# tinybord.net
KiCad netlist of a schematic drawn in Altium Designer
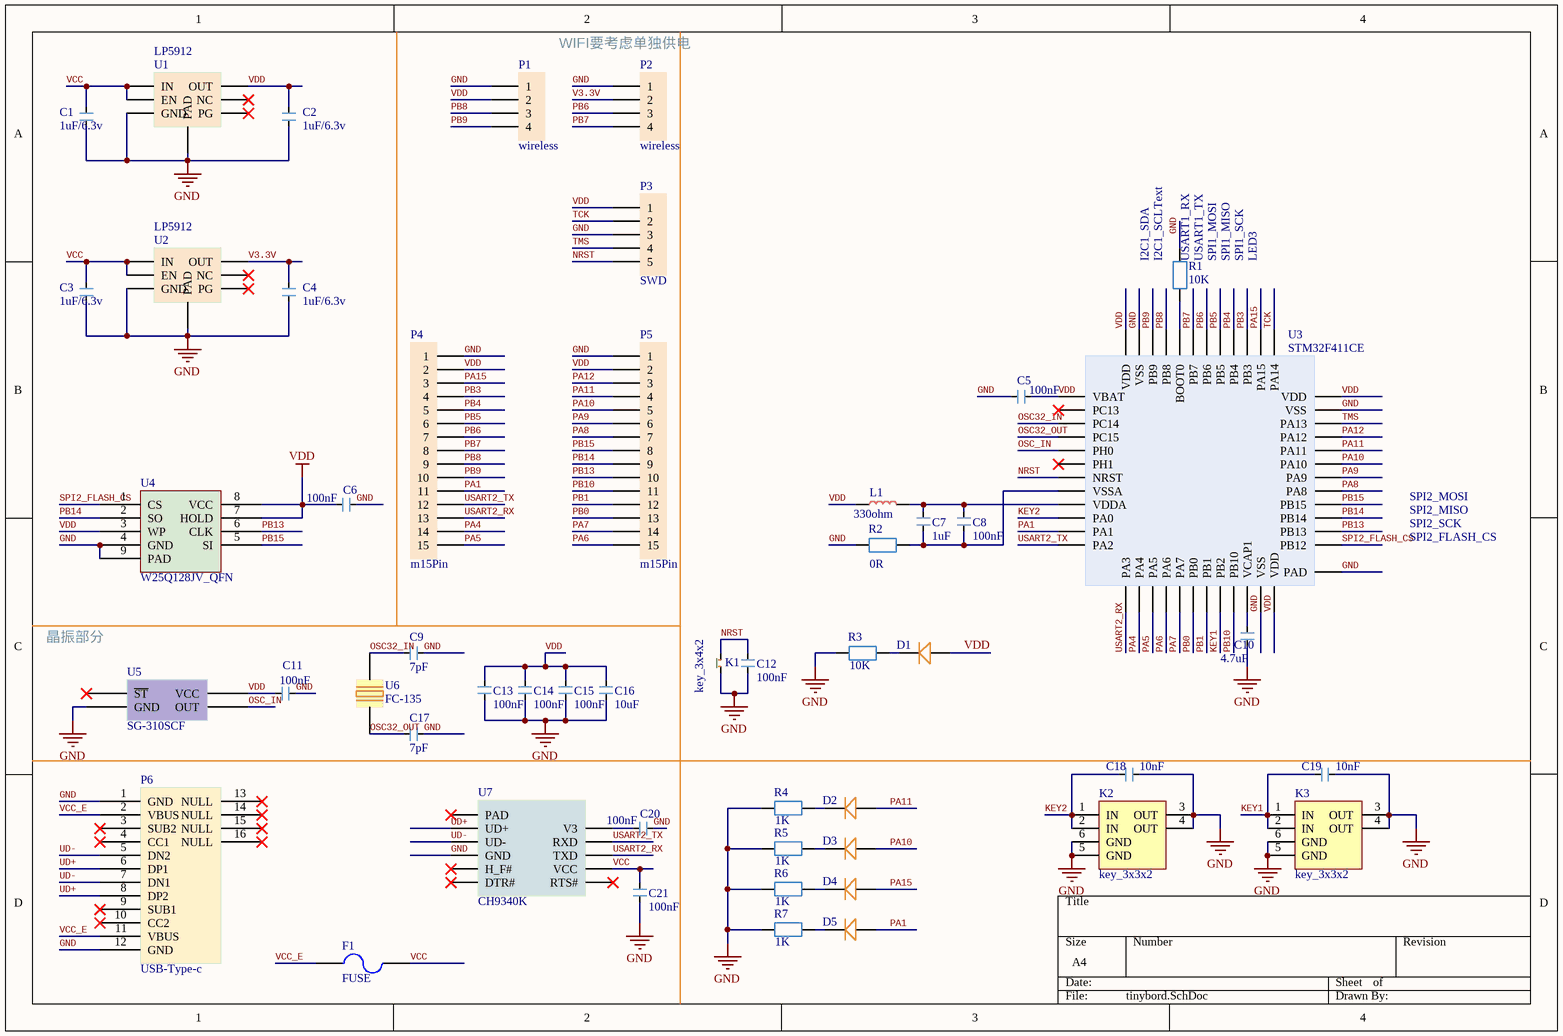
[diagram p0: tinybord.SchDoc]

(export (version "E")
  (design (tool "Eeschema 10.0.6"))
  (components
    (comp (ref "C1")
      (value "1uF/6.3v")
      (footprint "C0603")
      (description "陶瓷电容")
      (fields (field (name "Comment") "C0603"))
      (libsource (lib "DemoSchlib") (part "C0603"))
    )
    (comp (ref "C2")
      (value "1uF/6.3v")
      (footprint "C0603")
      (description "陶瓷电容")
      (fields (field (name "Comment") "C0603"))
      (libsource (lib "DemoSchlib") (part "C0603"))
    )
    (comp (ref "C3")
      (value "1uF/6.3v")
      (footprint "C0603")
      (description "陶瓷电容")
      (fields (field (name "Comment") "C0603"))
      (libsource (lib "DemoSchlib") (part "C0603"))
    )
    (comp (ref "C4")
      (value "1uF/6.3v")
      (footprint "C0603")
      (description "陶瓷电容")
      (fields (field (name "Comment") "C0603"))
      (libsource (lib "DemoSchlib") (part "C0603"))
    )
    (comp (ref "C5")
      (value "100nF")
      (footprint "C0603")
      (description "陶瓷电容")
      (fields (field (name "Comment") "C0603"))
      (libsource (lib "DemoSchlib") (part "C0603"))
    )
    (comp (ref "C6")
      (value "100nF")
      (footprint "C0603")
      (description "陶瓷电容")
      (fields (field (name "Comment") "C0603"))
      (libsource (lib "DemoSchlib") (part "C0603"))
    )
    (comp (ref "C7")
      (value "1uF")
      (footprint "C0603")
      (description "陶瓷电容")
      (fields (field (name "Comment") "C0603"))
      (libsource (lib "DemoSchlib") (part "C0603"))
    )
    (comp (ref "C8")
      (value "100nF")
      (footprint "C0603")
      (description "陶瓷电容")
      (fields (field (name "Comment") "C0603"))
      (libsource (lib "DemoSchlib") (part "C0603"))
    )
    (comp (ref "C9")
      (value "7pF")
      (footprint "C0603")
      (description "陶瓷电容")
      (fields (field (name "Comment") "C0603"))
      (libsource (lib "DemoSchlib") (part "C0603"))
    )
    (comp (ref "C10")
      (value "4.7uF")
      (footprint "C0603")
      (description "陶瓷电容")
      (fields (field (name "Comment") "C0603"))
      (libsource (lib "DemoSchlib") (part "C0603"))
    )
    (comp (ref "C11")
      (value "100nF")
      (footprint "C0603")
      (description "陶瓷电容")
      (fields (field (name "Comment") "C0603"))
      (libsource (lib "DemoSchlib") (part "C0603"))
    )
    (comp (ref "C12")
      (value "100nF")
      (footprint "C0603")
      (description "陶瓷电容")
      (fields (field (name "Comment") "C0603"))
      (libsource (lib "DemoSchlib") (part "C0603"))
    )
    (comp (ref "C13")
      (value "100nF")
      (footprint "C0603")
      (description "陶瓷电容")
      (fields (field (name "Comment") "C0603"))
      (libsource (lib "DemoSchlib") (part "C0603"))
    )
    (comp (ref "C14")
      (value "100nF")
      (footprint "C0603")
      (description "陶瓷电容")
      (fields (field (name "Comment") "C0603"))
      (libsource (lib "DemoSchlib") (part "C0603"))
    )
    (comp (ref "C15")
      (value "100nF")
      (footprint "C0603")
      (description "陶瓷电容")
      (fields (field (name "Comment") "C0603"))
      (libsource (lib "DemoSchlib") (part "C0603"))
    )
    (comp (ref "C16")
      (value "10uF")
      (footprint "C0603")
      (description "陶瓷电容")
      (fields (field (name "Comment") "C0603"))
      (libsource (lib "DemoSchlib") (part "C0603"))
    )
    (comp (ref "C17")
      (value "7pF")
      (footprint "C0603")
      (description "陶瓷电容")
      (fields (field (name "Comment") "C0603"))
      (libsource (lib "DemoSchlib") (part "C0603"))
    )
    (comp (ref "C18")
      (value "10nF")
      (footprint "C0603")
      (description "陶瓷电容")
      (fields (field (name "Comment") "C0603"))
      (libsource (lib "DemoSchlib") (part "C0603"))
    )
    (comp (ref "C19")
      (value "10nF")
      (footprint "C0603")
      (description "陶瓷电容")
      (fields (field (name "Comment") "C0603"))
      (libsource (lib "DemoSchlib") (part "C0603"))
    )
    (comp (ref "C20")
      (value "100nF")
      (footprint "C0603")
      (description "陶瓷电容")
      (fields (field (name "Comment") "C0603"))
      (libsource (lib "DemoSchlib") (part "C0603"))
    )
    (comp (ref "C21")
      (value "100nF")
      (footprint "C0603")
      (description "陶瓷电容")
      (fields (field (name "Comment") "C0603"))
      (libsource (lib "DemoSchlib") (part "C0603"))
    )
    (comp (ref "D1")
      (value "L0603")
      (footprint "led0603")
      (description "LED")
      (libsource (lib "DemoSchlib") (part "L0603"))
    )
    (comp (ref "D2")
      (value "L0603")
      (footprint "led0603")
      (description "LED")
      (libsource (lib "DemoSchlib") (part "L0603"))
    )
    (comp (ref "D3")
      (value "L0603")
      (footprint "led0603")
      (description "LED")
      (libsource (lib "DemoSchlib") (part "L0603"))
    )
    (comp (ref "D4")
      (value "L0603")
      (footprint "led0603")
      (description "LED")
      (libsource (lib "DemoSchlib") (part "L0603"))
    )
    (comp (ref "D5")
      (value "L0603")
      (footprint "led0603")
      (description "LED")
      (libsource (lib "DemoSchlib") (part "L0603"))
    )
    (comp (ref "F1")
      (value "FUSE")
      (footprint "R0603")
      (description "PTC 1812")
      (libsource (lib "DemoSchlib") (part "PTC0603"))
    )
    (comp (ref "K1")
      (value "key_3x4x2")
      (footprint "Key 3x4x2")
      (description "贴片按键")
      (libsource (lib "DemoSchlib") (part "key_3x4x2"))
    )
    (comp (ref "K2")
      (value "key_3x3x2")
      (footprint "Key 3x3x2")
      (description "贴片按键")
      (libsource (lib "DemoSchlib") (part "key_3x3x2"))
    )
    (comp (ref "K3")
      (value "key_3x3x2")
      (footprint "Key 3x3x2")
      (description "贴片按键")
      (libsource (lib "DemoSchlib") (part "key_3x3x2"))
    )
    (comp (ref "L1")
      (value "330ohm")
      (footprint "B0603")
      (description "磁珠")
      (fields (field (name "Comment") "B0603"))
      (libsource (lib "DemoSchlib") (part "B0603"))
    )
    (comp (ref "P1")
      (value "wireless")
      (footprint "4x1 header")
      (description "1x4pin 1.27mm")
      (libsource (lib "DemoSchlib") (part "m4Pin"))
    )
    (comp (ref "P2")
      (value "wireless")
      (footprint "4x1 header")
      (description "1x4pin 1.27mm")
      (libsource (lib "DemoSchlib") (part "m4Pin"))
    )
    (comp (ref "P3")
      (value "SWD")
      (footprint "5x1 header")
      (description "1x4pin 1.27mm")
      (libsource (lib "DemoSchlib") (part "m5Pin"))
    )
    (comp (ref "P4")
      (value "m15Pin")
      (footprint "15x1 header")
      (description "1x4pin 1.27mm")
      (libsource (lib "") (part "m15Pin_1"))
    )
    (comp (ref "P5")
      (value "m15Pin")
      (footprint "15x1 header")
      (description "1x4pin 1.27mm")
      (libsource (lib "DemoSchlib") (part "m15Pin"))
    )
    (comp (ref "P6")
      (value "USB-Type-c")
      (footprint "USB-TYPE-C")
      (description "use typec 16p")
      (libsource (lib "DemoSchlib") (part "USB-Type-c"))
    )
    (comp (ref "R1")
      (value "10K")
      (footprint "R0603")
      (description "电阻")
      (fields (field (name "Comment") "R0603"))
      (libsource (lib "DemoSchlib") (part "R0603"))
    )
    (comp (ref "R2")
      (value "0R")
      (footprint "R0603")
      (description "电阻")
      (fields (field (name "Comment") "R0603"))
      (libsource (lib "DemoSchlib") (part "R0603"))
    )
    (comp (ref "R3")
      (value "10K")
      (footprint "R0603")
      (description "电阻")
      (fields (field (name "Comment") "R0603"))
      (libsource (lib "DemoSchlib") (part "R0603"))
    )
    (comp (ref "R4")
      (value "1K")
      (footprint "R0603")
      (description "电阻")
      (fields (field (name "Comment") "R0603"))
      (libsource (lib "DemoSchlib") (part "R0603"))
    )
    (comp (ref "R5")
      (value "1K")
      (footprint "R0603")
      (description "电阻")
      (fields (field (name "Comment") "R0603"))
      (libsource (lib "DemoSchlib") (part "R0603"))
    )
    (comp (ref "R6")
      (value "1K")
      (footprint "R0603")
      (description "电阻")
      (fields (field (name "Comment") "R0603"))
      (libsource (lib "DemoSchlib") (part "R0603"))
    )
    (comp (ref "R7")
      (value "1K")
      (footprint "R0603")
      (description "电阻")
      (fields (field (name "Comment") "R0603"))
      (libsource (lib "DemoSchlib") (part "R0603"))
    )
    (comp (ref "U1")
      (value "LP5912")
      (footprint "LP5912")
      (description "LDO")
      (libsource (lib "DemoSchlib") (part "LP5912"))
    )
    (comp (ref "U2")
      (value "LP5912")
      (footprint "LP5912")
      (description "LDO")
      (libsource (lib "DemoSchlib") (part "LP5912"))
    )
    (comp (ref "U3")
      (value "STM32F411CE")
      (footprint "STM32F411CE QFN")
      (description "STM32F411 QFN48PIN")
      (libsource (lib "DemoSchlib") (part "STM32F411CE"))
    )
    (comp (ref "U4")
      (value "W25Q128JV_QFN")
      (footprint "W25Q64 QFN")
      (description "flash")
      (libsource (lib "DemoSchlib") (part "W25Q128JV_QFN"))
    )
    (comp (ref "U5")
      (value "SG-310SCF")
      (footprint "SG-310SCF")
      (description "有源晶振3225")
      (libsource (lib "DemoSchlib") (part "SG-310SCF"))
    )
    (comp (ref "U6")
      (value "FC-135")
      (footprint "FC-135")
      (description "32.768K无源晶振")
      (libsource (lib "DemoSchlib") (part "FC-135"))
    )
    (comp (ref "U7")
      (value "CH9340K")
      (footprint "CH9340")
      (description "USB转串口")
      (libsource (lib "DemoSchlib") (part "CH9340K"))
    )
  )
  (nets
    (net (code "1") (name "/KEY1") (class "Default")
      (node (ref "C19") (pin "2") (pintype "passive"))
      (node (ref "K3") (pin "1") (pinfunction "IN_1") (pintype "passive"))
      (node (ref "K3") (pin "2") (pinfunction "IN_2") (pintype "passive"))
      (node (ref "U3") (pin "20") (pinfunction "PB2_20") (pintype "passive"))
    )
    (net (code "2") (name "/KEY2") (class "Default")
      (node (ref "C18") (pin "2") (pintype "passive"))
      (node (ref "K2") (pin "1") (pinfunction "IN_1") (pintype "passive"))
      (node (ref "K2") (pin "2") (pinfunction "IN_2") (pintype "passive"))
      (node (ref "U3") (pin "10") (pinfunction "PA0_10") (pintype "passive"))
    )
    (net (code "3") (name "/NRST") (class "Default")
      (node (ref "C12") (pin "2") (pintype "passive"))
      (node (ref "K1") (pin "2") (pintype "passive"))
      (node (ref "P3") (pin "5") (pinfunction "5_5") (pintype "passive"))
      (node (ref "U3") (pin "7") (pinfunction "NRST_7") (pintype "passive"))
    )
    (net (code "4") (name "/OSC32_IN") (class "Default")
      (node (ref "C9") (pin "2") (pintype "passive"))
      (node (ref "U3") (pin "3") (pinfunction "PC14_3") (pintype "passive"))
      (node (ref "U6") (pin "2") (pintype "passive"))
    )
    (net (code "5") (name "/OSC32_OUT") (class "Default")
      (node (ref "C17") (pin "2") (pintype "passive"))
      (node (ref "U3") (pin "4") (pinfunction "PC15_4") (pintype "passive"))
      (node (ref "U6") (pin "1") (pintype "passive"))
    )
    (net (code "6") (name "/OSC_IN") (class "Default")
      (node (ref "U3") (pin "5") (pinfunction "PH0_5") (pintype "passive"))
      (node (ref "U5") (pin "3") (pinfunction "OUT_3") (pintype "passive"))
    )
    (net (code "7") (name "/PA1") (class "Default")
      (node (ref "D5") (pin "2") (pintype "passive"))
      (node (ref "P4") (pin "11") (pinfunction "11_11") (pintype "passive"))
      (node (ref "U3") (pin "11") (pinfunction "PA1_11") (pintype "passive"))
    )
    (net (code "8") (name "/PA4") (class "Default")
      (node (ref "P4") (pin "14") (pinfunction "14_14") (pintype "passive"))
      (node (ref "U3") (pin "14") (pinfunction "PA4_14") (pintype "passive"))
    )
    (net (code "9") (name "/PA5") (class "Default")
      (node (ref "P4") (pin "15") (pinfunction "15_15") (pintype "passive"))
      (node (ref "U3") (pin "15") (pinfunction "PA5_15") (pintype "passive"))
    )
    (net (code "10") (name "/PA6") (class "Default")
      (node (ref "P5") (pin "15") (pinfunction "15_15") (pintype "passive"))
      (node (ref "U3") (pin "16") (pinfunction "PA6_16") (pintype "passive"))
    )
    (net (code "11") (name "/PA7") (class "Default")
      (node (ref "P5") (pin "14") (pinfunction "14_14") (pintype "passive"))
      (node (ref "U3") (pin "17") (pinfunction "PA7_17") (pintype "passive"))
    )
    (net (code "12") (name "/PA8") (class "Default")
      (node (ref "P5") (pin "7") (pinfunction "7_7") (pintype "passive"))
      (node (ref "U3") (pin "29") (pinfunction "PA8_29") (pintype "passive"))
    )
    (net (code "13") (name "/PA9") (class "Default")
      (node (ref "P5") (pin "6") (pinfunction "6_6") (pintype "passive"))
      (node (ref "U3") (pin "30") (pinfunction "PA9_30") (pintype "passive"))
    )
    (net (code "14") (name "/PA10") (class "Default")
      (node (ref "D3") (pin "2") (pintype "passive"))
      (node (ref "P5") (pin "5") (pinfunction "5_5") (pintype "passive"))
      (node (ref "U3") (pin "31") (pinfunction "PA10_31") (pintype "passive"))
    )
    (net (code "15") (name "/PA11") (class "Default")
      (node (ref "D2") (pin "2") (pintype "passive"))
      (node (ref "P5") (pin "4") (pinfunction "4_4") (pintype "passive"))
      (node (ref "U3") (pin "32") (pinfunction "PA11_32") (pintype "passive"))
    )
    (net (code "16") (name "/PA12") (class "Default")
      (node (ref "P5") (pin "3") (pinfunction "3_3") (pintype "passive"))
      (node (ref "U3") (pin "33") (pinfunction "PA12_33") (pintype "passive"))
    )
    (net (code "17") (name "/PA15") (class "Default")
      (node (ref "D4") (pin "2") (pintype "passive"))
      (node (ref "P4") (pin "3") (pinfunction "3_3") (pintype "passive"))
      (node (ref "U3") (pin "38") (pinfunction "PA15_38") (pintype "passive"))
    )
    (net (code "18") (name "/PB0") (class "Default")
      (node (ref "P5") (pin "13") (pinfunction "13_13") (pintype "passive"))
      (node (ref "U3") (pin "18") (pinfunction "PB0_18") (pintype "passive"))
    )
    (net (code "19") (name "/PB1") (class "Default")
      (node (ref "P5") (pin "12") (pinfunction "12_12") (pintype "passive"))
      (node (ref "U3") (pin "19") (pinfunction "PB1_19") (pintype "passive"))
    )
    (net (code "20") (name "/PB3") (class "Default")
      (node (ref "P4") (pin "4") (pinfunction "4_4") (pintype "passive"))
      (node (ref "U3") (pin "39") (pinfunction "PB3_39") (pintype "passive"))
    )
    (net (code "21") (name "/PB4") (class "Default")
      (node (ref "P4") (pin "5") (pinfunction "5_5") (pintype "passive"))
      (node (ref "U3") (pin "40") (pinfunction "PB4_40") (pintype "passive"))
    )
    (net (code "22") (name "/PB5") (class "Default")
      (node (ref "P4") (pin "6") (pinfunction "6_6") (pintype "passive"))
      (node (ref "U3") (pin "41") (pinfunction "PB5_41") (pintype "passive"))
    )
    (net (code "23") (name "/PB6") (class "Default")
      (node (ref "P2") (pin "3") (pinfunction "3_3") (pintype "passive"))
      (node (ref "P4") (pin "7") (pinfunction "7_7") (pintype "passive"))
      (node (ref "U3") (pin "42") (pinfunction "PB6_42") (pintype "passive"))
    )
    (net (code "24") (name "/PB7") (class "Default")
      (node (ref "P2") (pin "4") (pinfunction "4_4") (pintype "passive"))
      (node (ref "P4") (pin "8") (pinfunction "8_8") (pintype "passive"))
      (node (ref "U3") (pin "43") (pinfunction "PB7_43") (pintype "passive"))
    )
    (net (code "25") (name "/PB8") (class "Default")
      (node (ref "P1") (pin "3") (pinfunction "3_3") (pintype "passive"))
      (node (ref "P4") (pin "9") (pinfunction "9_9") (pintype "passive"))
      (node (ref "U3") (pin "45") (pinfunction "PB8_45") (pintype "passive"))
    )
    (net (code "26") (name "/PB9") (class "Default")
      (node (ref "P1") (pin "4") (pinfunction "4_4") (pintype "passive"))
      (node (ref "P4") (pin "10") (pinfunction "10_10") (pintype "passive"))
      (node (ref "U3") (pin "46") (pinfunction "PB9_46") (pintype "passive"))
    )
    (net (code "27") (name "/PB10") (class "Default")
      (node (ref "P5") (pin "11") (pinfunction "11_11") (pintype "passive"))
      (node (ref "U3") (pin "21") (pinfunction "PB10_21") (pintype "passive"))
    )
    (net (code "28") (name "/PB13") (class "Default")
      (node (ref "P5") (pin "10") (pinfunction "10_10") (pintype "passive"))
      (node (ref "U3") (pin "26") (pinfunction "PB13_26") (pintype "passive"))
      (node (ref "U4") (pin "6") (pinfunction "CLK_6") (pintype "passive"))
    )
    (net (code "29") (name "/PB14") (class "Default")
      (node (ref "P5") (pin "9") (pinfunction "9_9") (pintype "passive"))
      (node (ref "U3") (pin "27") (pinfunction "PB14_27") (pintype "passive"))
      (node (ref "U4") (pin "2") (pinfunction "SO_2") (pintype "passive"))
    )
    (net (code "30") (name "/PB15") (class "Default")
      (node (ref "P5") (pin "8") (pinfunction "8_8") (pintype "passive"))
      (node (ref "U3") (pin "28") (pinfunction "PB15_28") (pintype "passive"))
      (node (ref "U4") (pin "5") (pinfunction "SI_5") (pintype "passive"))
    )
    (net (code "31") (name "/SPI2_FLASH_CS") (class "Default")
      (node (ref "U3") (pin "25") (pinfunction "PB12_25") (pintype "passive"))
      (node (ref "U4") (pin "1") (pinfunction "CS_1") (pintype "passive"))
    )
    (net (code "32") (name "/TCK") (class "Default")
      (node (ref "P3") (pin "2") (pinfunction "2_2") (pintype "passive"))
      (node (ref "U3") (pin "37") (pinfunction "PA14_37") (pintype "passive"))
    )
    (net (code "33") (name "/TMS") (class "Default")
      (node (ref "P3") (pin "4") (pinfunction "4_4") (pintype "passive"))
      (node (ref "U3") (pin "34") (pinfunction "PA13_34") (pintype "passive"))
    )
    (net (code "34") (name "/UD+") (class "Default")
      (node (ref "P6") (pin "6") (pinfunction "DP1_6") (pintype "passive"))
      (node (ref "P6") (pin "8") (pinfunction "DP2_8") (pintype "passive"))
      (node (ref "U7") (pin "1") (pinfunction "UD+_1") (pintype "passive"))
    )
    (net (code "35") (name "/UD-") (class "Default")
      (node (ref "P6") (pin "5") (pinfunction "DN2_5") (pintype "passive"))
      (node (ref "P6") (pin "7") (pinfunction "DN1_7") (pintype "passive"))
      (node (ref "U7") (pin "2") (pinfunction "UD-_2") (pintype "passive"))
    )
    (net (code "36") (name "/USART2_RX") (class "Default")
      (node (ref "P4") (pin "13") (pinfunction "13_13") (pintype "passive"))
      (node (ref "U3") (pin "13") (pinfunction "PA3_13") (pintype "passive"))
      (node (ref "U7") (pin "8") (pinfunction "TXD_8") (pintype "passive"))
    )
    (net (code "37") (name "/USART2_TX") (class "Default")
      (node (ref "P4") (pin "12") (pinfunction "12_12") (pintype "passive"))
      (node (ref "U3") (pin "12") (pinfunction "PA2_12") (pintype "passive"))
      (node (ref "U7") (pin "9") (pinfunction "RXD_9") (pintype "passive"))
    )
    (net (code "38") (name "/V3.3V") (class "Default")
      (node (ref "C4") (pin "2") (pintype "passive"))
      (node (ref "P2") (pin "2") (pinfunction "2_2") (pintype "passive"))
      (node (ref "U2") (pin "1") (pinfunction "OUT_1") (pintype "passive"))
    )
    (net (code "39") (name "/VCC") (class "Default")
      (node (ref "C1") (pin "2") (pintype "passive"))
      (node (ref "C21") (pin "2") (pintype "passive"))
      (node (ref "C3") (pin "2") (pintype "passive"))
      (node (ref "F1") (pin "2") (pinfunction "2_2") (pintype "passive"))
      (node (ref "U1") (pin "4") (pinfunction "EN_4") (pintype "passive"))
      (node (ref "U1") (pin "6") (pinfunction "IN_6") (pintype "passive"))
      (node (ref "U2") (pin "4") (pinfunction "EN_4") (pintype "passive"))
      (node (ref "U2") (pin "6") (pinfunction "IN_6") (pintype "passive"))
      (node (ref "U7") (pin "7") (pinfunction "VCC_7") (pintype "passive"))
    )
    (net (code "40") (name "/VCC_E") (class "Default")
      (node (ref "F1") (pin "1") (pinfunction "1_1") (pintype "passive"))
      (node (ref "P6") (pin "11") (pinfunction "VBUS_11") (pintype "passive"))
      (node (ref "P6") (pin "2") (pinfunction "VBUS_2") (pintype "passive"))
    )
    (net (code "41") (name "GND") (class "Default")
      (node (ref "C1") (pin "1") (pintype "passive"))
      (node (ref "C10") (pin "1") (pintype "passive"))
      (node (ref "C11") (pin "2") (pintype "passive"))
      (node (ref "C12") (pin "1") (pintype "passive"))
      (node (ref "C13") (pin "1") (pintype "passive"))
      (node (ref "C14") (pin "1") (pintype "passive"))
      (node (ref "C15") (pin "1") (pintype "passive"))
      (node (ref "C16") (pin "1") (pintype "passive"))
      (node (ref "C17") (pin "1") (pintype "passive"))
      (node (ref "C18") (pin "1") (pintype "passive"))
      (node (ref "C19") (pin "1") (pintype "passive"))
      (node (ref "C2") (pin "1") (pintype "passive"))
      (node (ref "C20") (pin "2") (pintype "passive"))
      (node (ref "C21") (pin "1") (pintype "passive"))
      (node (ref "C3") (pin "1") (pintype "passive"))
      (node (ref "C4") (pin "1") (pintype "passive"))
      (node (ref "C5") (pin "1") (pintype "passive"))
      (node (ref "C6") (pin "2") (pintype "passive"))
      (node (ref "C9") (pin "1") (pintype "passive"))
      (node (ref "K1") (pin "1") (pintype "passive"))
      (node (ref "K2") (pin "3") (pinfunction "OUT_3") (pintype "passive"))
      (node (ref "K2") (pin "4") (pinfunction "OUT_4") (pintype "passive"))
      (node (ref "K2") (pin "5") (pinfunction "GND_5") (pintype "passive"))
      (node (ref "K2") (pin "6") (pinfunction "GND_6") (pintype "passive"))
      (node (ref "K3") (pin "3") (pinfunction "OUT_3") (pintype "passive"))
      (node (ref "K3") (pin "4") (pinfunction "OUT_4") (pintype "passive"))
      (node (ref "K3") (pin "5") (pinfunction "GND_5") (pintype "passive"))
      (node (ref "K3") (pin "6") (pinfunction "GND_6") (pintype "passive"))
      (node (ref "P1") (pin "1") (pinfunction "1_1") (pintype "passive"))
      (node (ref "P2") (pin "1") (pinfunction "1_1") (pintype "passive"))
      (node (ref "P3") (pin "3") (pinfunction "3_3") (pintype "passive"))
      (node (ref "P4") (pin "1") (pinfunction "1_1") (pintype "passive"))
      (node (ref "P5") (pin "1") (pinfunction "1_1") (pintype "passive"))
      (node (ref "P6") (pin "1") (pinfunction "GND_1") (pintype "passive"))
      (node (ref "P6") (pin "12") (pinfunction "GND_12") (pintype "passive"))
      (node (ref "R1") (pin "2") (pintype "passive"))
      (node (ref "R2") (pin "1") (pintype "passive"))
      (node (ref "R3") (pin "1") (pintype "passive"))
      (node (ref "R4") (pin "1") (pintype "passive"))
      (node (ref "R5") (pin "1") (pintype "passive"))
      (node (ref "R6") (pin "1") (pintype "passive"))
      (node (ref "R7") (pin "1") (pintype "passive"))
      (node (ref "U1") (pin "5") (pinfunction "GND_5") (pintype "passive"))
      (node (ref "U1") (pin "7") (pinfunction "PAD_7") (pintype "passive"))
      (node (ref "U2") (pin "5") (pinfunction "GND_5") (pintype "passive"))
      (node (ref "U2") (pin "7") (pinfunction "PAD_7") (pintype "passive"))
      (node (ref "U3") (pin "23") (pinfunction "VSS_23") (pintype "passive"))
      (node (ref "U3") (pin "35") (pinfunction "VSS_35") (pintype "passive"))
      (node (ref "U3") (pin "47") (pinfunction "VSS_47") (pintype "passive"))
      (node (ref "U3") (pin "49") (pinfunction "PAD_49") (pintype "passive"))
      (node (ref "U4") (pin "4") (pinfunction "GND_4") (pintype "passive"))
      (node (ref "U4") (pin "9") (pinfunction "PAD_9") (pintype "passive"))
      (node (ref "U5") (pin "2") (pinfunction "GND_2") (pintype "passive"))
      (node (ref "U7") (pin "3") (pinfunction "GND_3") (pintype "passive"))
    )
    (net (code "42") (name "Net-(D1-Pad1)") (class "Default")
      (node (ref "D1") (pin "1") (pintype "passive"))
      (node (ref "R3") (pin "2") (pintype "passive"))
    )
    (net (code "43") (name "Net-(D2-Pad1)") (class "Default")
      (node (ref "D2") (pin "1") (pintype "passive"))
      (node (ref "R4") (pin "2") (pintype "passive"))
    )
    (net (code "44") (name "Net-(D3-Pad1)") (class "Default")
      (node (ref "D3") (pin "1") (pintype "passive"))
      (node (ref "R5") (pin "2") (pintype "passive"))
    )
    (net (code "45") (name "Net-(D4-Pad1)") (class "Default")
      (node (ref "D4") (pin "1") (pintype "passive"))
      (node (ref "R6") (pin "2") (pintype "passive"))
    )
    (net (code "46") (name "Net-(D5-Pad1)") (class "Default")
      (node (ref "D5") (pin "1") (pintype "passive"))
      (node (ref "R7") (pin "2") (pintype "passive"))
    )
    (net (code "47") (name "Net-(U3-BOOT0)") (class "Default")
      (node (ref "R1") (pin "1") (pintype "passive"))
      (node (ref "U3") (pin "44") (pinfunction "BOOT0_44") (pintype "passive"))
    )
    (net (code "48") (name "Net-(U3-VCAP1)") (class "Default")
      (node (ref "C10") (pin "2") (pintype "passive"))
      (node (ref "U3") (pin "22") (pinfunction "VCAP1_22") (pintype "passive"))
    )
    (net (code "49") (name "Net-(U3-VDDA)") (class "Default")
      (node (ref "C7") (pin "2") (pintype "passive"))
      (node (ref "C8") (pin "2") (pintype "passive"))
      (node (ref "L1") (pin "2") (pintype "passive"))
      (node (ref "U3") (pin "9") (pinfunction "VDDA_9") (pintype "passive"))
    )
    (net (code "50") (name "Net-(U3-VSSA)") (class "Default")
      (node (ref "C7") (pin "1") (pintype "passive"))
      (node (ref "C8") (pin "1") (pintype "passive"))
      (node (ref "R2") (pin "2") (pintype "passive"))
      (node (ref "U3") (pin "8") (pinfunction "VSSA_8") (pintype "passive"))
    )
    (net (code "51") (name "Net-(U7-V3)") (class "Default")
      (node (ref "C20") (pin "1") (pintype "passive"))
      (node (ref "U7") (pin "10") (pinfunction "V3_10") (pintype "passive"))
    )
    (net (code "52") (name "VDD") (class "Default")
      (node (ref "C11") (pin "1") (pintype "passive"))
      (node (ref "C13") (pin "2") (pintype "passive"))
      (node (ref "C14") (pin "2") (pintype "passive"))
      (node (ref "C15") (pin "2") (pintype "passive"))
      (node (ref "C16") (pin "2") (pintype "passive"))
      (node (ref "C2") (pin "2") (pintype "passive"))
      (node (ref "C5") (pin "2") (pintype "passive"))
      (node (ref "C6") (pin "1") (pintype "passive"))
      (node (ref "D1") (pin "2") (pintype "passive"))
      (node (ref "L1") (pin "1") (pintype "passive"))
      (node (ref "P1") (pin "2") (pinfunction "2_2") (pintype "passive"))
      (node (ref "P3") (pin "1") (pinfunction "1_1") (pintype "passive"))
      (node (ref "P4") (pin "2") (pinfunction "2_2") (pintype "passive"))
      (node (ref "P5") (pin "2") (pinfunction "2_2") (pintype "passive"))
      (node (ref "U1") (pin "1") (pinfunction "OUT_1") (pintype "passive"))
      (node (ref "U3") (pin "1") (pinfunction "VBAT_1") (pintype "passive"))
      (node (ref "U3") (pin "24") (pinfunction "VDD_24") (pintype "passive"))
      (node (ref "U3") (pin "36") (pinfunction "VDD_36") (pintype "passive"))
      (node (ref "U3") (pin "48") (pinfunction "VDD_48") (pintype "passive"))
      (node (ref "U4") (pin "3") (pinfunction "WP_3") (pintype "passive"))
      (node (ref "U4") (pin "7") (pinfunction "HOLD_7") (pintype "passive"))
      (node (ref "U4") (pin "8") (pinfunction "VCC_8") (pintype "passive"))
      (node (ref "U5") (pin "4") (pinfunction "VCC_4") (pintype "passive"))
    )
    (net (code "53") (name "unconnected-(P6-CC1-Pad4)") (class "Default")
      (node (ref "P6") (pin "4") (pinfunction "CC1_4") (pintype "passive+no_connect"))
    )
    (net (code "54") (name "unconnected-(P6-CC2-Pad10)") (class "Default")
      (node (ref "P6") (pin "10") (pinfunction "CC2_10") (pintype "passive+no_connect"))
    )
    (net (code "55") (name "unconnected-(P6-NULL-Pad13)") (class "Default")
      (node (ref "P6") (pin "13") (pinfunction "NULL_13") (pintype "passive+no_connect"))
    )
    (net (code "56") (name "unconnected-(P6-NULL-Pad14)") (class "Default")
      (node (ref "P6") (pin "14") (pinfunction "NULL_14") (pintype "passive+no_connect"))
    )
    (net (code "57") (name "unconnected-(P6-NULL-Pad15)") (class "Default")
      (node (ref "P6") (pin "15") (pinfunction "NULL_15") (pintype "passive+no_connect"))
    )
    (net (code "58") (name "unconnected-(P6-NULL-Pad16)") (class "Default")
      (node (ref "P6") (pin "16") (pinfunction "NULL_16") (pintype "passive+no_connect"))
    )
    (net (code "59") (name "unconnected-(P6-SUB1-Pad9)") (class "Default")
      (node (ref "P6") (pin "9") (pinfunction "SUB1_9") (pintype "passive+no_connect"))
    )
    (net (code "60") (name "unconnected-(P6-SUB2-Pad3)") (class "Default")
      (node (ref "P6") (pin "3") (pinfunction "SUB2_3") (pintype "passive+no_connect"))
    )
    (net (code "61") (name "unconnected-(U1-NC-Pad2)") (class "Default")
      (node (ref "U1") (pin "2") (pinfunction "NC_2") (pintype "passive+no_connect"))
    )
    (net (code "62") (name "unconnected-(U1-PG-Pad3)") (class "Default")
      (node (ref "U1") (pin "3") (pinfunction "PG_3") (pintype "passive+no_connect"))
    )
    (net (code "63") (name "unconnected-(U2-NC-Pad2)") (class "Default")
      (node (ref "U2") (pin "2") (pinfunction "NC_2") (pintype "passive+no_connect"))
    )
    (net (code "64") (name "unconnected-(U2-PG-Pad3)") (class "Default")
      (node (ref "U2") (pin "3") (pinfunction "PG_3") (pintype "passive+no_connect"))
    )
    (net (code "65") (name "unconnected-(U3-PC13-Pad2)") (class "Default")
      (node (ref "U3") (pin "2") (pinfunction "PC13_2") (pintype "passive+no_connect"))
    )
    (net (code "66") (name "unconnected-(U3-PH1-Pad6)") (class "Default")
      (node (ref "U3") (pin "6") (pinfunction "PH1_6") (pintype "passive+no_connect"))
    )
    (net (code "67") (name "unconnected-(U5-~{ST}-Pad1)") (class "Default")
      (node (ref "U5") (pin "1") (pinfunction "~{ST}_1") (pintype "passive+no_connect"))
    )
    (net (code "68") (name "unconnected-(U7-DTR#-Pad5)") (class "Default")
      (node (ref "U7") (pin "5") (pinfunction "DTR#_5") (pintype "passive+no_connect"))
    )
    (net (code "69") (name "unconnected-(U7-H_F#-Pad4)") (class "Default")
      (node (ref "U7") (pin "4") (pinfunction "H_F#_4") (pintype "passive+no_connect"))
    )
    (net (code "70") (name "unconnected-(U7-PAD-Pad11)") (class "Default")
      (node (ref "U7") (pin "11") (pinfunction "PAD_11") (pintype "passive+no_connect"))
    )
    (net (code "71") (name "unconnected-(U7-RTS#-Pad6)") (class "Default")
      (node (ref "U7") (pin "6") (pinfunction "RTS#_6") (pintype "passive+no_connect"))
    )
  )
)
